# Multivibrator.net
KiCad netlist of a schematic drawn in Altium Designer
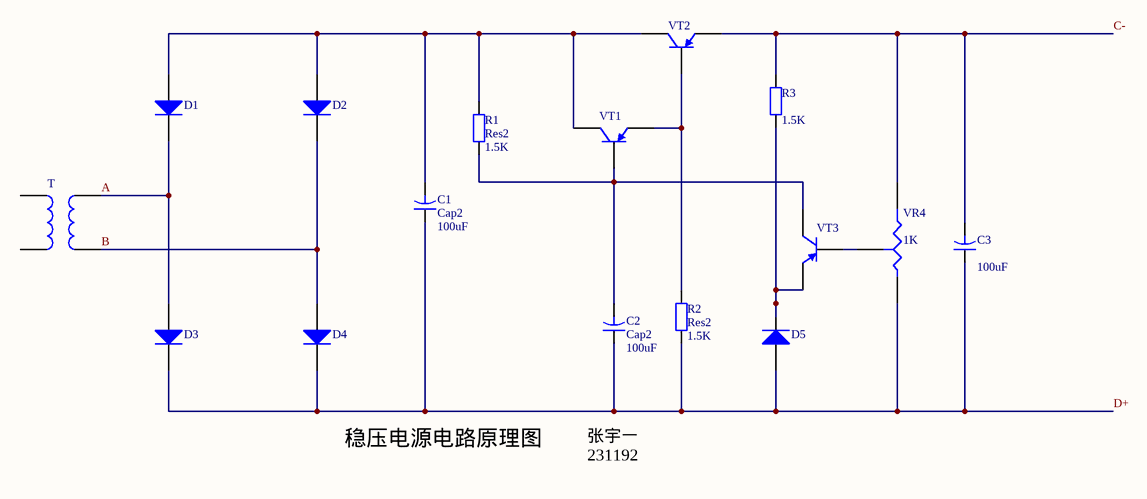
[diagram p0: Multivibrator.SchDoc]

(export (version "E")
  (design (tool "Eeschema 10.0.6"))
  (components
    (comp (ref "C1")
      (value "Cap2")
      (footprint "RAD-0.3")
      (description "Capacitor")
      (fields (field (name "ALTIUM_VALUE") "100uF") (field (name "PUBLISHER") "Altium Limited"))
      (libsource (lib "Miscellaneous Devices") (part "Cap2"))
    )
    (comp (ref "C2")
      (value "Cap2")
      (footprint "RAD-0.3")
      (description "Capacitor")
      (fields (field (name "ALTIUM_VALUE") "100uF") (field (name "PUBLISHER") "Altium Limited"))
      (libsource (lib "Miscellaneous Devices") (part "Cap2"))
    )
    (comp (ref "C3")
      (value "100uF")
      (footprint "RAD-0.3")
      (description "Capacitor")
      (fields (field (name "Comment") "Cap2") (field (name "PUBLISHER") "Altium Limited"))
      (libsource (lib "Miscellaneous Devices") (part "Cap2"))
    )
    (comp (ref "D1")
      (value "Diode 1N4004")
      (footprint "DIODE-0.4")
      (description "1 Amp General Purpose Rectifier")
      (fields (field (name "PUBLISHER") "Altium Limited"))
      (libsource (lib "Miscellaneous Devices") (part "Diode 1N4004"))
    )
    (comp (ref "D2")
      (value "Diode 1N4004")
      (footprint "DIODE-0.4")
      (description "1 Amp General Purpose Rectifier")
      (fields (field (name "PUBLISHER") "Altium Limited"))
      (libsource (lib "Miscellaneous Devices") (part "Diode 1N4004"))
    )
    (comp (ref "D3")
      (value "Diode 1N4004")
      (footprint "DIODE-0.4")
      (description "1 Amp General Purpose Rectifier")
      (fields (field (name "PUBLISHER") "Altium Limited"))
      (libsource (lib "Miscellaneous Devices") (part "Diode 1N4004"))
    )
    (comp (ref "D4")
      (value "Diode 1N4004")
      (footprint "DIODE-0.4")
      (description "1 Amp General Purpose Rectifier")
      (fields (field (name "PUBLISHER") "Altium Limited"))
      (libsource (lib "Miscellaneous Devices") (part "Diode 1N4004"))
    )
    (comp (ref "D5")
      (value "Diode 1N4004")
      (footprint "DIODE-0.4")
      (description "1 Amp General Purpose Rectifier")
      (fields (field (name "PUBLISHER") "Altium Limited"))
      (libsource (lib "Miscellaneous Devices") (part "Diode 1N4004"))
    )
    (comp (ref "R1")
      (value "Res2")
      (footprint "AXIAL-0.3")
      (description "Resistor")
      (fields (field (name "ALTIUM_VALUE") "1.5K") (field (name "PUBLISHER") "Altium Limited"))
      (libsource (lib "Miscellaneous Devices") (part "Res2"))
    )
    (comp (ref "R2")
      (value "Res2")
      (footprint "AXIAL-0.3")
      (description "Resistor")
      (fields (field (name "ALTIUM_VALUE") "1.5K") (field (name "PUBLISHER") "Altium Limited"))
      (libsource (lib "Miscellaneous Devices") (part "Res2"))
    )
    (comp (ref "R3")
      (value "1.5K")
      (footprint "AXIAL-0.3")
      (description "Resistor")
      (fields (field (name "Comment") "Res2") (field (name "PUBLISHER") "Altium Limited"))
      (libsource (lib "Miscellaneous Devices") (part "Res2"))
    )
    (comp (ref "T")
      (value "Trans")
      (footprint "TRANS")
      (description "Transformer")
      (fields (field (name "PUBLISHER") "Altium Limited"))
      (libsource (lib "Miscellaneous Devices") (part "Trans"))
    )
    (comp (ref "VR4")
      (value "1K")
      (footprint "VR3")
      (description "Tapped Resistor")
      (fields (field (name "Comment") "Res Tap") (field (name "PUBLISHER") "Altium Limited"))
      (libsource (lib "Miscellaneous Devices") (part "Res Tap"))
    )
    (comp (ref "VT1")
      (value "2N3906")
      (footprint "TO92A")
      (description "PNP General Purpose Amplifier")
      (fields (field (name "PUBLISHER") "Altium Limited"))
      (libsource (lib "Miscellaneous Devices") (part "2N3906"))
    )
    (comp (ref "VT2")
      (value "2N3906")
      (footprint "TO92A")
      (description "PNP General Purpose Amplifier")
      (fields (field (name "PUBLISHER") "Altium Limited"))
      (libsource (lib "Miscellaneous Devices") (part "2N3906"))
    )
    (comp (ref "VT3")
      (value "2N3906")
      (footprint "TO92A")
      (description "PNP General Purpose Amplifier")
      (fields (field (name "PUBLISHER") "Altium Limited"))
      (libsource (lib "Miscellaneous Devices") (part "2N3906"))
    )
  )
  (nets
    (net (code "1") (name "/A") (class "Default")
      (node (ref "D1") (pin "2") (pinfunction "K_2") (pintype "passive"))
      (node (ref "D3") (pin "1") (pinfunction "A_1") (pintype "passive"))
      (node (ref "T") (pin "3") (pinfunction "3_3") (pintype "passive"))
    )
    (net (code "2") (name "/B") (class "Default")
      (node (ref "D2") (pin "2") (pinfunction "K_2") (pintype "passive"))
      (node (ref "D4") (pin "1") (pinfunction "A_1") (pintype "passive"))
      (node (ref "T") (pin "4") (pinfunction "4_4") (pintype "passive"))
    )
    (net (code "3") (name "/C-") (class "Default")
      (node (ref "C3") (pin "2") (pinfunction "2_2") (pintype "passive"))
      (node (ref "R3") (pin "2") (pinfunction "2_2") (pintype "passive"))
      (node (ref "VR4") (pin "2") (pinfunction "B_2") (pintype "passive"))
      (node (ref "VT2") (pin "1") (pinfunction "E_1") (pintype "passive"))
    )
    (net (code "4") (name "/D+") (class "Default")
      (node (ref "C1") (pin "1") (pinfunction "1_1") (pintype "passive"))
      (node (ref "C2") (pin "1") (pinfunction "1_1") (pintype "passive"))
      (node (ref "C3") (pin "1") (pinfunction "1_1") (pintype "passive"))
      (node (ref "D3") (pin "2") (pinfunction "K_2") (pintype "passive"))
      (node (ref "D4") (pin "2") (pinfunction "K_2") (pintype "passive"))
      (node (ref "D5") (pin "1") (pinfunction "A_1") (pintype "passive"))
      (node (ref "R2") (pin "1") (pinfunction "1_1") (pintype "passive"))
      (node (ref "VR4") (pin "1") (pinfunction "A_1") (pintype "passive"))
    )
    (net (code "5") (name "Net-(D1-A)") (class "Default")
      (node (ref "C1") (pin "2") (pinfunction "2_2") (pintype "passive"))
      (node (ref "D1") (pin "1") (pinfunction "A_1") (pintype "passive"))
      (node (ref "D2") (pin "1") (pinfunction "A_1") (pintype "passive"))
      (node (ref "R1") (pin "2") (pinfunction "2_2") (pintype "passive"))
      (node (ref "VT1") (pin "3") (pinfunction "C_3") (pintype "passive"))
      (node (ref "VT2") (pin "3") (pinfunction "C_3") (pintype "passive"))
    )
    (net (code "6") (name "Net-(D5-K)") (class "Default")
      (node (ref "D5") (pin "2") (pinfunction "K_2") (pintype "passive"))
      (node (ref "R3") (pin "1") (pinfunction "1_1") (pintype "passive"))
      (node (ref "VT3") (pin "1") (pinfunction "E_1") (pintype "passive"))
    )
    (net (code "7") (name "Net-(VR4-TAP)") (class "Default")
      (node (ref "VR4") (pin "3") (pinfunction "TAP_3") (pintype "passive"))
      (node (ref "VT3") (pin "2") (pinfunction "B_2") (pintype "passive"))
    )
    (net (code "8") (name "Net-(VT1-B)") (class "Default")
      (node (ref "C2") (pin "2") (pinfunction "2_2") (pintype "passive"))
      (node (ref "R1") (pin "1") (pinfunction "1_1") (pintype "passive"))
      (node (ref "VT1") (pin "2") (pinfunction "B_2") (pintype "passive"))
      (node (ref "VT3") (pin "3") (pinfunction "C_3") (pintype "passive"))
    )
    (net (code "9") (name "Net-(VT1-E)") (class "Default")
      (node (ref "R2") (pin "2") (pinfunction "2_2") (pintype "passive"))
      (node (ref "VT1") (pin "1") (pinfunction "E_1") (pintype "passive"))
      (node (ref "VT2") (pin "2") (pinfunction "B_2") (pintype "passive"))
    )
    (net (code "10") (name "unconnected-(T-Pad1)") (class "Default")
      (node (ref "T") (pin "1") (pinfunction "1_1") (pintype "passive"))
    )
    (net (code "11") (name "unconnected-(T-Pad2)") (class "Default")
      (node (ref "T") (pin "2") (pinfunction "2_2") (pintype "passive"))
    )
  )
)
